# Mirror_TurnSignal.net
KiCad netlist of a schematic drawn in Altium Designer
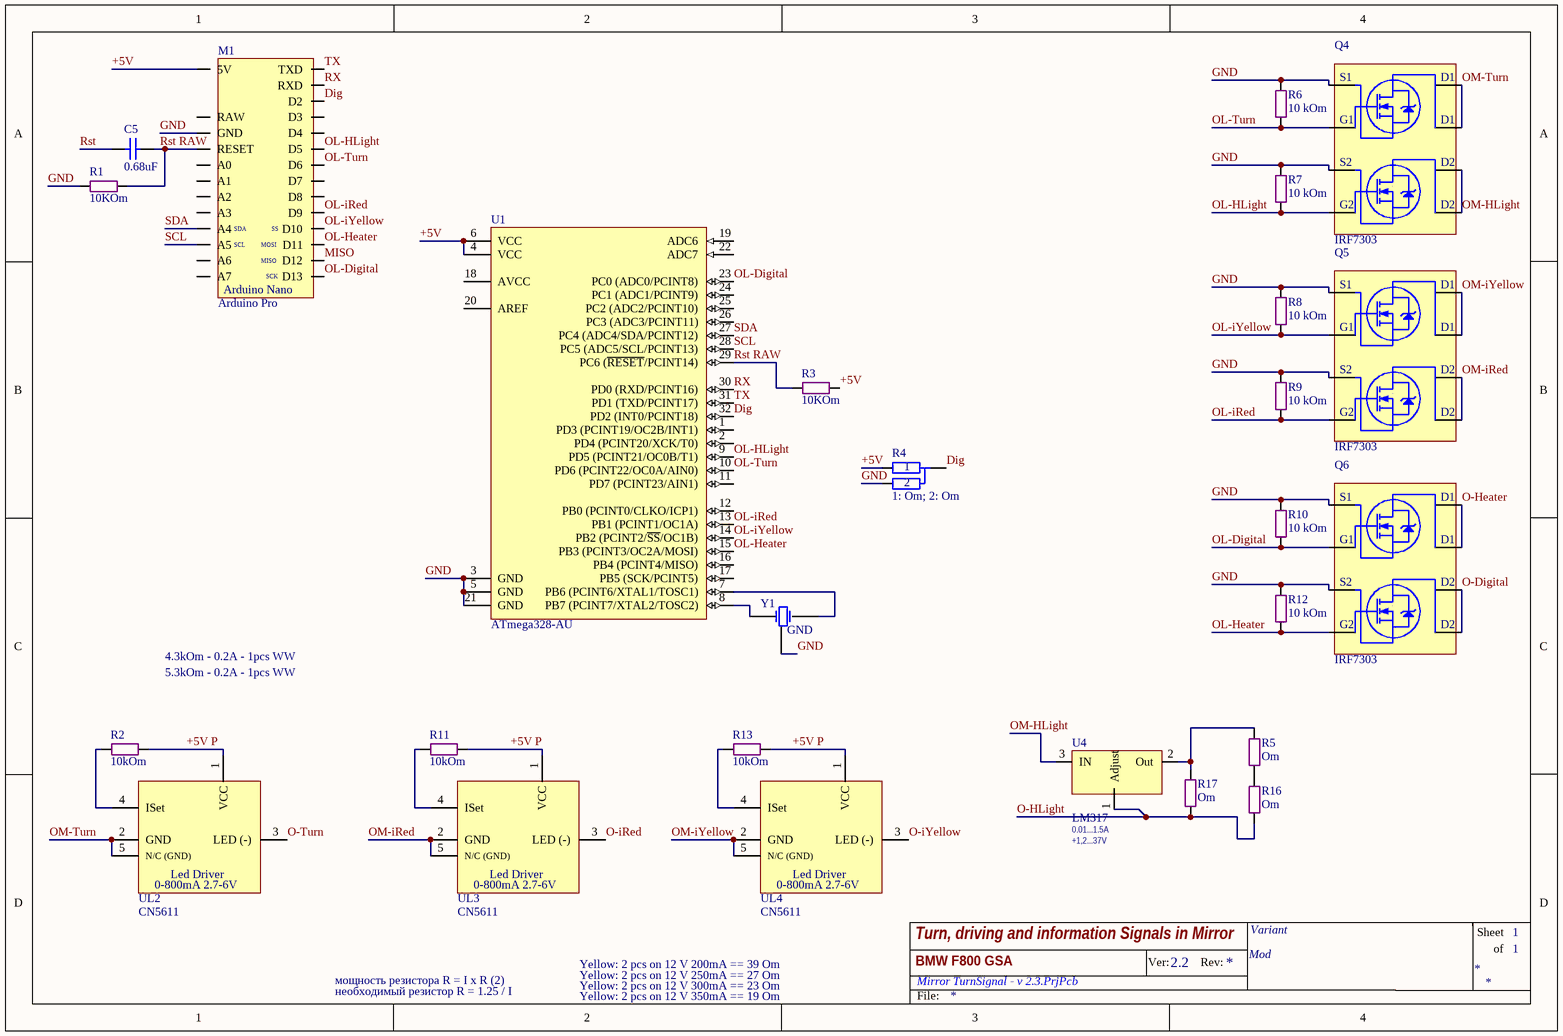
[diagram p0: Mirror TurnSignal.SchDoc]

(export (version "E")
  (design (tool "Eeschema 10.0.6"))
  (components
    (comp (ref "C5")
      (value "0.68uF")
      (footprint "Capacitor:SMD 0805 (2012)")
      (description "Capacitor")
      (libsource (lib "Capacitor") (part "Cap SMD 0402-1812"))
    )
    (comp (ref "M1")
      (value "Arduino Pro")
      (footprint "Modules:Arduino Pro Mini Low (no A0-3,6-7,D3)")
      (libsource (lib "Modules") (part "Arduino Pro Micro"))
    )
    (comp (ref "Q4")
      (value "IRF7303")
      (footprint "GeneralCases:SO8")
      (description "Dual N-Ch  30V - 0.05Ω - 4.9A")
      (fields (field (name "MANUFACTURER") "Farchild"))
      (libsource (lib "Transistor") (part "IRF7303"))
    )
    (comp (ref "Q5")
      (value "IRF7303")
      (footprint "GeneralCases:SO8")
      (description "Dual N-Ch  30V - 0.05Ω - 4.9A")
      (fields (field (name "MANUFACTURER") "Farchild"))
      (libsource (lib "Transistor") (part "IRF7303"))
    )
    (comp (ref "Q6")
      (value "IRF7303")
      (footprint "GeneralCases:SO8")
      (description "Dual N-Ch  30V - 0.05Ω - 4.9A")
      (fields (field (name "MANUFACTURER") "Farchild"))
      (libsource (lib "Transistor") (part "IRF7303"))
    )
    (comp (ref "R1")
      (value "10KOm")
      (footprint "PassiveComponents:SMD 0805 (2012)")
      (libsource (lib "PassiveComponents") (part "Res All Types"))
    )
    (comp (ref "R2")
      (value "10kOm")
      (footprint "PassiveComponents:SMD 0805 (2012)")
      (libsource (lib "PassiveComponents") (part "Res All Types"))
    )
    (comp (ref "R3")
      (value "10KOm")
      (footprint "PassiveComponents:SMD 0805 (2012)")
      (libsource (lib "PassiveComponents") (part "Res All Types"))
    )
    (comp (ref "R4")
      (value "1: Om; 2: Om")
      (footprint "PassiveComponents:SMD 0805 (2012) Double")
      (description "Choice from two resistors")
      (libsource (lib "PassiveComponents") (part "Res SMD (Select one way)"))
    )
    (comp (ref "R5")
      (value "Om")
      (footprint "PassiveComponents:Res 5W L22mm, p22.86")
      (description "5W Cement")
      (libsource (lib "PassiveComponents") (part "Res 5W"))
    )
    (comp (ref "R6")
      (value "10 kOm")
      (footprint "PassiveComponents:SMD 0805 (2012)")
      (libsource (lib "PassiveComponents") (part "Res All Types"))
    )
    (comp (ref "R7")
      (value "10 kOm")
      (footprint "PassiveComponents:SMD 0805 (2012)")
      (libsource (lib "PassiveComponents") (part "Res All Types"))
    )
    (comp (ref "R8")
      (value "10 kOm")
      (footprint "PassiveComponents:SMD 0805 (2012)")
      (libsource (lib "PassiveComponents") (part "Res All Types"))
    )
    (comp (ref "R9")
      (value "10 kOm")
      (footprint "PassiveComponents:SMD 0805 (2012)")
      (libsource (lib "PassiveComponents") (part "Res All Types"))
    )
    (comp (ref "R10")
      (value "10 kOm")
      (footprint "PassiveComponents:SMD 0805 (2012)")
      (libsource (lib "PassiveComponents") (part "Res All Types"))
    )
    (comp (ref "R11")
      (value "10kOm")
      (footprint "PassiveComponents:SMD 0805 (2012)")
      (libsource (lib "PassiveComponents") (part "Res All Types"))
    )
    (comp (ref "R12")
      (value "10 kOm")
      (footprint "PassiveComponents:SMD 0805 (2012)")
      (libsource (lib "PassiveComponents") (part "Res All Types"))
    )
    (comp (ref "R13")
      (value "10kOm")
      (footprint "PassiveComponents:SMD 0805 (2012)")
      (libsource (lib "PassiveComponents") (part "Res All Types"))
    )
    (comp (ref "R16")
      (value "Om")
      (footprint "PassiveComponents:Res 5W L22mm, p22.86")
      (description "5W Cement")
      (libsource (lib "PassiveComponents") (part "Res 5W"))
    )
    (comp (ref "R17")
      (value "Om")
      (footprint "PassiveComponents:Res 10W L48mm, p49mm")
      (description "10W Cement")
      (libsource (lib "PassiveComponents") (part "Res 10W"))
    )
    (comp (ref "U1")
      (value "ATmega328-AU")
      (footprint "32A_M")
      (fields (field (name "PUBLISHER") "Altium Limited"))
      (libsource (lib "Atmel Microcontroller 8-Bit megaAVR") (part "ATmega328-AU"))
    )
    (comp (ref "U4")
      (value "LM317")
      (footprint "GeneralCases:TO220 L")
      (description "Voltage Regulator")
      (fields (field (name "I OUTPUT (A) ADJUSTABLE") "0.01...1.5A") (field (name "V OUT") "+1,2...37V"))
      (libsource (lib "PowerAdjusment") (part "LM-317"))
    )
    (comp (ref "UL2")
      (value "CN5611")
      (footprint "GeneralCases:SOT-89-5")
      (description "Led Driver 0-800mA 2.7-6V")
      (fields (field (name "NAME") "CN5611"))
      (libsource (lib "Chips") (part "CN5611"))
    )
    (comp (ref "UL3")
      (value "CN5611")
      (footprint "GeneralCases:SOT-89-5")
      (description "Led Driver 0-800mA 2.7-6V")
      (fields (field (name "NAME") "CN5611"))
      (libsource (lib "Chips") (part "CN5611"))
    )
    (comp (ref "UL4")
      (value "CN5611")
      (footprint "GeneralCases:SOT-89-5")
      (description "Led Driver 0-800mA 2.7-6V")
      (fields (field (name "NAME") "CN5611"))
      (libsource (lib "Chips") (part "CN5611"))
    )
    (comp (ref "Y1")
      (value "16MHz")
      (footprint "PassiveComponents:XTAL - 3.2x1.2 SMD ws GND")
      (description "3 Pin with Capacitors")
      (libsource (lib "PassiveComponents") (part "XTAL ws CAP"))
    )
  )
  (nets
    (net (code "1") (name "/+5V") (class "Default")
      (node (ref "M1") (pin "5V") (pinfunction "5V_5V") (pintype "passive"))
      (node (ref "R3") (pin "2") (pinfunction "2_2") (pintype "passive"))
      (node (ref "R4") (pin "1") (pinfunction "1_1") (pintype "passive"))
      (node (ref "U1") (pin "4") (pinfunction "VCC_4") (pintype "power_in"))
      (node (ref "U1") (pin "6") (pinfunction "VCC_6") (pintype "power_in"))
    )
    (net (code "2") (name "/+5V P") (class "Default")
      (node (ref "R11") (pin "1") (pinfunction "1_1") (pintype "passive"))
      (node (ref "R13") (pin "1") (pinfunction "1_1") (pintype "passive"))
      (node (ref "R2") (pin "1") (pinfunction "1_1") (pintype "passive"))
      (node (ref "UL2") (pin "1") (pinfunction "VCC_1") (pintype "power_in"))
      (node (ref "UL3") (pin "1") (pinfunction "VCC_1") (pintype "power_in"))
      (node (ref "UL4") (pin "1") (pinfunction "VCC_1") (pintype "power_in"))
    )
    (net (code "3") (name "/Dig") (class "Default")
      (node (ref "M1") (pin "D2") (pinfunction "D2_D2") (pintype "passive"))
      (node (ref "R4") (pin "3") (pinfunction "3_3") (pintype "passive"))
      (node (ref "U1") (pin "32") (pinfunction "PD2_(INT0/PCINT18)_32") (pintype "bidirectional"))
    )
    (net (code "4") (name "/GND") (class "Default")
      (node (ref "M1") (pin "GND") (pinfunction "GND_GND") (pintype "passive"))
      (node (ref "Q4") (pin "1") (pinfunction "S_1") (pintype "passive"))
      (node (ref "Q4") (pin "3") (pinfunction "S_3") (pintype "passive"))
      (node (ref "Q5") (pin "1") (pinfunction "S_1") (pintype "passive"))
      (node (ref "Q5") (pin "3") (pinfunction "S_3") (pintype "passive"))
      (node (ref "Q6") (pin "1") (pinfunction "S_1") (pintype "passive"))
      (node (ref "Q6") (pin "3") (pinfunction "S_3") (pintype "passive"))
      (node (ref "R1") (pin "1") (pinfunction "1_1") (pintype "passive"))
      (node (ref "R10") (pin "2") (pinfunction "2_2") (pintype "passive"))
      (node (ref "R12") (pin "2") (pinfunction "2_2") (pintype "passive"))
      (node (ref "R4") (pin "2") (pinfunction "2_2") (pintype "passive"))
      (node (ref "R6") (pin "2") (pinfunction "2_2") (pintype "passive"))
      (node (ref "R7") (pin "2") (pinfunction "2_2") (pintype "passive"))
      (node (ref "R8") (pin "2") (pinfunction "2_2") (pintype "passive"))
      (node (ref "R9") (pin "2") (pinfunction "2_2") (pintype "passive"))
      (node (ref "U1") (pin "21") (pinfunction "GND_21") (pintype "power_in"))
      (node (ref "U1") (pin "3") (pinfunction "GND_3") (pintype "power_in"))
      (node (ref "U1") (pin "5") (pinfunction "GND_5") (pintype "power_in"))
      (node (ref "Y1") (pin "3") (pinfunction "GND_3") (pintype "passive"))
    )
    (net (code "5") (name "/MISO") (class "Default")
      (node (ref "M1") (pin "D12") (pinfunction "D12_D12") (pintype "passive"))
    )
    (net (code "6") (name "/O-Digital") (class "Default")
      (node (ref "Q6") (pin "5") (pinfunction "D_5") (pintype "passive"))
      (node (ref "Q6") (pin "6") (pinfunction "D_6") (pintype "passive"))
    )
    (net (code "7") (name "/O-HLight") (class "Default")
      (node (ref "R16") (pin "1") (pinfunction "1_1") (pintype "passive"))
      (node (ref "R17") (pin "1") (pinfunction "1_1") (pintype "passive"))
      (node (ref "U4") (pin "1") (pinfunction "Adjust_1") (pintype "passive"))
    )
    (net (code "8") (name "/O-Heater") (class "Default")
      (node (ref "Q6") (pin "7") (pinfunction "D_7") (pintype "passive"))
      (node (ref "Q6") (pin "8") (pinfunction "D_8") (pintype "passive"))
    )
    (net (code "9") (name "/O-Turn") (class "Default")
      (node (ref "UL2") (pin "3") (pinfunction "LED_(-)_3") (pintype "power_in"))
    )
    (net (code "10") (name "/O-iRed") (class "Default")
      (node (ref "UL3") (pin "3") (pinfunction "LED_(-)_3") (pintype "power_in"))
    )
    (net (code "11") (name "/O-iYellow") (class "Default")
      (node (ref "UL4") (pin "3") (pinfunction "LED_(-)_3") (pintype "power_in"))
    )
    (net (code "12") (name "/OL-Digital") (class "Default")
      (node (ref "M1") (pin "D13") (pinfunction "D13_D13") (pintype "passive"))
      (node (ref "Q6") (pin "2") (pinfunction "G_2") (pintype "passive"))
      (node (ref "R10") (pin "1") (pinfunction "1_1") (pintype "passive"))
      (node (ref "U1") (pin "23") (pinfunction "PC0_(ADC0/PCINT8)_23") (pintype "bidirectional"))
    )
    (net (code "13") (name "/OL-HLight") (class "Default")
      (node (ref "M1") (pin "D5") (pinfunction "D5_D5") (pintype "passive"))
      (node (ref "Q4") (pin "4") (pinfunction "G_4") (pintype "passive"))
      (node (ref "R7") (pin "1") (pinfunction "1_1") (pintype "passive"))
      (node (ref "U1") (pin "9") (pinfunction "PD5_(PCINT21/OC0B/T1)_9") (pintype "bidirectional"))
    )
    (net (code "14") (name "/OL-Heater") (class "Default")
      (node (ref "M1") (pin "D11") (pinfunction "D11_D11") (pintype "passive"))
      (node (ref "Q6") (pin "4") (pinfunction "G_4") (pintype "passive"))
      (node (ref "R12") (pin "1") (pinfunction "1_1") (pintype "passive"))
      (node (ref "U1") (pin "15") (pinfunction "PB3_(PCINT3/OC2A/MOSI)_15") (pintype "bidirectional"))
    )
    (net (code "15") (name "/OL-Turn") (class "Default")
      (node (ref "M1") (pin "D6") (pinfunction "D6_D6") (pintype "passive"))
      (node (ref "Q4") (pin "2") (pinfunction "G_2") (pintype "passive"))
      (node (ref "R6") (pin "1") (pinfunction "1_1") (pintype "passive"))
      (node (ref "U1") (pin "10") (pinfunction "PD6_(PCINT22/OC0A/AIN0)_10") (pintype "bidirectional"))
    )
    (net (code "16") (name "/OL-iRed") (class "Default")
      (node (ref "M1") (pin "D9") (pinfunction "D9_D9") (pintype "passive"))
      (node (ref "Q5") (pin "4") (pinfunction "G_4") (pintype "passive"))
      (node (ref "R9") (pin "1") (pinfunction "1_1") (pintype "passive"))
      (node (ref "U1") (pin "13") (pinfunction "PB1_(PCINT1/OC1A)_13") (pintype "bidirectional"))
    )
    (net (code "17") (name "/OL-iYellow") (class "Default")
      (node (ref "M1") (pin "D10") (pinfunction "D10_D10") (pintype "passive"))
      (node (ref "Q5") (pin "2") (pinfunction "G_2") (pintype "passive"))
      (node (ref "R8") (pin "1") (pinfunction "1_1") (pintype "passive"))
      (node (ref "U1") (pin "14") (pinfunction "PB2_(PCINT2/~{SS}/OC1B)_14") (pintype "bidirectional"))
    )
    (net (code "18") (name "/OM-HLight") (class "Default")
      (node (ref "Q4") (pin "5") (pinfunction "D_5") (pintype "passive"))
      (node (ref "Q4") (pin "6") (pinfunction "D_6") (pintype "passive"))
      (node (ref "U4") (pin "3") (pinfunction "IN_3") (pintype "power_in"))
    )
    (net (code "19") (name "/OM-Turn") (class "Default")
      (node (ref "Q4") (pin "7") (pinfunction "D_7") (pintype "passive"))
      (node (ref "Q4") (pin "8") (pinfunction "D_8") (pintype "passive"))
      (node (ref "UL2") (pin "2") (pinfunction "GND_2") (pintype "power_in"))
      (node (ref "UL2") (pin "5") (pinfunction "N/C_(GND)_5") (pintype "power_in"))
    )
    (net (code "20") (name "/OM-iRed") (class "Default")
      (node (ref "Q5") (pin "5") (pinfunction "D_5") (pintype "passive"))
      (node (ref "Q5") (pin "6") (pinfunction "D_6") (pintype "passive"))
      (node (ref "UL3") (pin "2") (pinfunction "GND_2") (pintype "power_in"))
      (node (ref "UL3") (pin "5") (pinfunction "N/C_(GND)_5") (pintype "power_in"))
    )
    (net (code "21") (name "/OM-iYellow") (class "Default")
      (node (ref "Q5") (pin "7") (pinfunction "D_7") (pintype "passive"))
      (node (ref "Q5") (pin "8") (pinfunction "D_8") (pintype "passive"))
      (node (ref "UL4") (pin "2") (pinfunction "GND_2") (pintype "power_in"))
      (node (ref "UL4") (pin "5") (pinfunction "N/C_(GND)_5") (pintype "power_in"))
    )
    (net (code "22") (name "/RX") (class "Default")
      (node (ref "M1") (pin "RXD") (pinfunction "RXD_RXD") (pintype "passive"))
      (node (ref "U1") (pin "30") (pinfunction "PD0_(RXD/PCINT16)_30") (pintype "bidirectional"))
    )
    (net (code "23") (name "/Rst") (class "Default")
      (node (ref "C5") (pin "1") (pinfunction "1_1") (pintype "passive"))
    )
    (net (code "24") (name "/Rst RAW") (class "Default")
      (node (ref "C5") (pin "2") (pinfunction "2_2") (pintype "passive"))
      (node (ref "M1") (pin "RESET") (pinfunction "RESET_RESET") (pintype "passive"))
      (node (ref "R1") (pin "2") (pinfunction "2_2") (pintype "passive"))
      (node (ref "R3") (pin "1") (pinfunction "1_1") (pintype "passive"))
      (node (ref "U1") (pin "29") (pinfunction "PC6_(~{RESET}/PCINT14)_29") (pintype "bidirectional"))
    )
    (net (code "25") (name "/SCL") (class "Default")
      (node (ref "M1") (pin "A5") (pinfunction "A5_A5") (pintype "passive"))
      (node (ref "U1") (pin "28") (pinfunction "PC5_(ADC5/SCL/PCINT13)_28") (pintype "bidirectional"))
    )
    (net (code "26") (name "/SDA") (class "Default")
      (node (ref "M1") (pin "A4") (pinfunction "A4_A4") (pintype "passive"))
      (node (ref "U1") (pin "27") (pinfunction "PC4_(ADC4/SDA/PCINT12)_27") (pintype "bidirectional"))
    )
    (net (code "27") (name "/TX") (class "Default")
      (node (ref "M1") (pin "TXD") (pinfunction "TXD_TXD") (pintype "passive"))
      (node (ref "U1") (pin "31") (pinfunction "PD1_(TXD/PCINT17)_31") (pintype "bidirectional"))
    )
    (net (code "28") (name "Net-(R16-Pad2)") (class "Default")
      (node (ref "R16") (pin "2") (pinfunction "2_2") (pintype "passive"))
      (node (ref "R5") (pin "1") (pinfunction "1_1") (pintype "passive"))
    )
    (net (code "29") (name "Net-(U1-PB6_(PCINT6{slash}XTAL1{slash}TOSC1))") (class "Default")
      (node (ref "U1") (pin "7") (pinfunction "PB6_(PCINT6/XTAL1/TOSC1)_7") (pintype "bidirectional"))
      (node (ref "Y1") (pin "2") (pinfunction "OSC2_2") (pintype "passive"))
    )
    (net (code "30") (name "Net-(U1-PB7_(PCINT7{slash}XTAL2{slash}TOSC2))") (class "Default")
      (node (ref "U1") (pin "8") (pinfunction "PB7_(PCINT7/XTAL2/TOSC2)_8") (pintype "bidirectional"))
      (node (ref "Y1") (pin "1") (pinfunction "OSC1_1") (pintype "passive"))
    )
    (net (code "31") (name "Net-(U4-Out)") (class "Default")
      (node (ref "R17") (pin "2") (pinfunction "2_2") (pintype "passive"))
      (node (ref "R5") (pin "2") (pinfunction "2_2") (pintype "passive"))
      (node (ref "U4") (pin "2") (pinfunction "Out_2") (pintype "power_in"))
    )
    (net (code "32") (name "Net-(UL2-ISet)") (class "Default")
      (node (ref "R2") (pin "2") (pinfunction "2_2") (pintype "passive"))
      (node (ref "UL2") (pin "4") (pinfunction "ISet_4") (pintype "power_in"))
    )
    (net (code "33") (name "Net-(UL3-ISet)") (class "Default")
      (node (ref "R11") (pin "2") (pinfunction "2_2") (pintype "passive"))
      (node (ref "UL3") (pin "4") (pinfunction "ISet_4") (pintype "power_in"))
    )
    (net (code "34") (name "Net-(UL4-ISet)") (class "Default")
      (node (ref "R13") (pin "2") (pinfunction "2_2") (pintype "passive"))
      (node (ref "UL4") (pin "4") (pinfunction "ISet_4") (pintype "power_in"))
    )
    (net (code "35") (name "unconnected-(M1-PadA0)") (class "Default")
      (node (ref "M1") (pin "A0") (pinfunction "A0_A0") (pintype "passive"))
    )
    (net (code "36") (name "unconnected-(M1-PadA1)") (class "Default")
      (node (ref "M1") (pin "A1") (pinfunction "A1_A1") (pintype "passive"))
    )
    (net (code "37") (name "unconnected-(M1-PadA2)") (class "Default")
      (node (ref "M1") (pin "A2") (pinfunction "A2_A2") (pintype "passive"))
    )
    (net (code "38") (name "unconnected-(M1-PadA3)") (class "Default")
      (node (ref "M1") (pin "A3") (pinfunction "A3_A3") (pintype "passive"))
    )
    (net (code "39") (name "unconnected-(M1-PadA6)") (class "Default")
      (node (ref "M1") (pin "A6") (pinfunction "A6_A6") (pintype "passive"))
    )
    (net (code "40") (name "unconnected-(M1-PadA7)") (class "Default")
      (node (ref "M1") (pin "A7") (pinfunction "A7_A7") (pintype "passive"))
    )
    (net (code "41") (name "unconnected-(M1-PadD3)") (class "Default")
      (node (ref "M1") (pin "D3") (pinfunction "D3_D3") (pintype "passive"))
    )
    (net (code "42") (name "unconnected-(M1-PadD4)") (class "Default")
      (node (ref "M1") (pin "D4") (pinfunction "D4_D4") (pintype "passive"))
    )
    (net (code "43") (name "unconnected-(M1-PadD7)") (class "Default")
      (node (ref "M1") (pin "D7") (pinfunction "D7_D7") (pintype "passive"))
    )
    (net (code "44") (name "unconnected-(M1-PadD8)") (class "Default")
      (node (ref "M1") (pin "D8") (pinfunction "D8_D8") (pintype "passive"))
    )
    (net (code "45") (name "unconnected-(M1-PadRAW)") (class "Default")
      (node (ref "M1") (pin "RAW") (pinfunction "RAW_RAW") (pintype "passive"))
    )
    (net (code "46") (name "unconnected-(U1-ADC6-Pad19)") (class "Default")
      (node (ref "U1") (pin "19") (pinfunction "ADC6_19") (pintype "input"))
    )
    (net (code "47") (name "unconnected-(U1-ADC7-Pad22)") (class "Default")
      (node (ref "U1") (pin "22") (pinfunction "ADC7_22") (pintype "input"))
    )
    (net (code "48") (name "unconnected-(U1-AREF-Pad20)") (class "Default")
      (node (ref "U1") (pin "20") (pinfunction "AREF_20") (pintype "passive"))
    )
    (net (code "49") (name "unconnected-(U1-AVCC-Pad18)") (class "Default")
      (node (ref "U1") (pin "18") (pinfunction "AVCC_18") (pintype "power_in"))
    )
    (net (code "50") (name "unconnected-(U1-PB0_(PCINT0{slash}CLKO{slash}ICP1)-Pad12)") (class "Default")
      (node (ref "U1") (pin "12") (pinfunction "PB0_(PCINT0/CLKO/ICP1)_12") (pintype "bidirectional"))
    )
    (net (code "51") (name "unconnected-(U1-PB4_(PCINT4{slash}MISO)-Pad16)") (class "Default")
      (node (ref "U1") (pin "16") (pinfunction "PB4_(PCINT4/MISO)_16") (pintype "bidirectional"))
    )
    (net (code "52") (name "unconnected-(U1-PB5_(SCK{slash}PCINT5)-Pad17)") (class "Default")
      (node (ref "U1") (pin "17") (pinfunction "PB5_(SCK/PCINT5)_17") (pintype "bidirectional"))
    )
    (net (code "53") (name "unconnected-(U1-PC1_(ADC1{slash}PCINT9)-Pad24)") (class "Default")
      (node (ref "U1") (pin "24") (pinfunction "PC1_(ADC1/PCINT9)_24") (pintype "bidirectional"))
    )
    (net (code "54") (name "unconnected-(U1-PC2_(ADC2{slash}PCINT10)-Pad25)") (class "Default")
      (node (ref "U1") (pin "25") (pinfunction "PC2_(ADC2/PCINT10)_25") (pintype "bidirectional"))
    )
    (net (code "55") (name "unconnected-(U1-PC3_(ADC3{slash}PCINT11)-Pad26)") (class "Default")
      (node (ref "U1") (pin "26") (pinfunction "PC3_(ADC3/PCINT11)_26") (pintype "bidirectional"))
    )
    (net (code "56") (name "unconnected-(U1-PD3_(PCINT19{slash}OC2B{slash}INT1)-Pad1)") (class "Default")
      (node (ref "U1") (pin "1") (pinfunction "PD3_(PCINT19/OC2B/INT1)_1") (pintype "bidirectional"))
    )
    (net (code "57") (name "unconnected-(U1-PD4_(PCINT20{slash}XCK{slash}T0)-Pad2)") (class "Default")
      (node (ref "U1") (pin "2") (pinfunction "PD4_(PCINT20/XCK/T0)_2") (pintype "bidirectional"))
    )
    (net (code "58") (name "unconnected-(U1-PD7_(PCINT23{slash}AIN1)-Pad11)") (class "Default")
      (node (ref "U1") (pin "11") (pinfunction "PD7_(PCINT23/AIN1)_11") (pintype "bidirectional"))
    )
  )
)
